# untitled.net
KiCad netlist of a schematic drawn in EAGLE
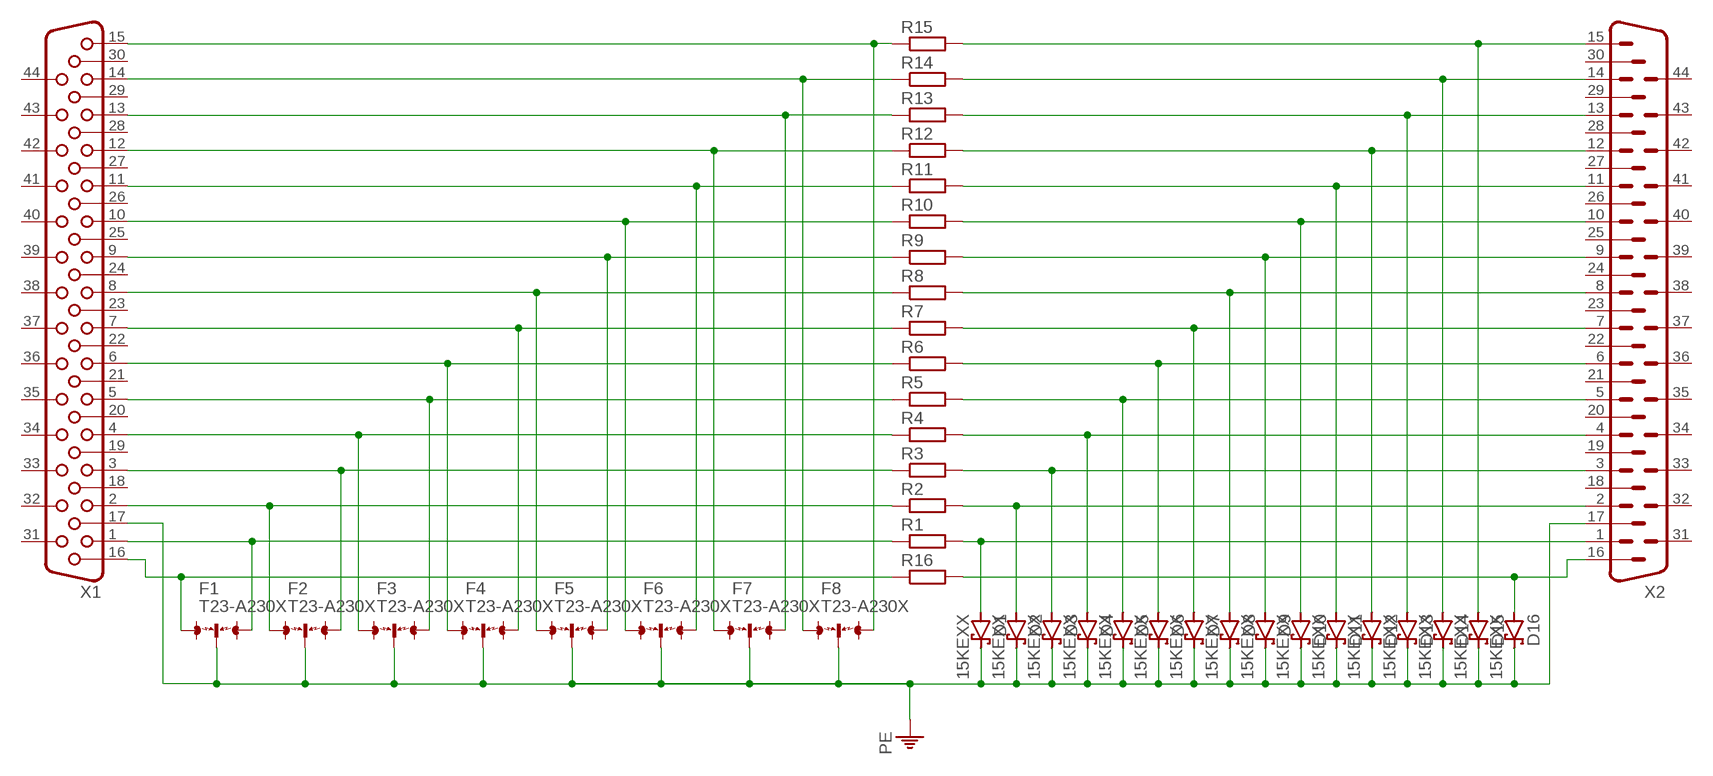
[diagram p0: schematic, sheet 1]

(export (version "E")
  (design (tool "Eeschema 10.0.6"))
  (components
    (comp (ref "D1")
      (value "15KEXX")
      (footprint "eagle-import:CB429-17")
      (libsource (lib "eagle-import") (part "15KEXX"))
    )
    (comp (ref "D2")
      (value "15KEXX")
      (footprint "eagle-import:CB429-17")
      (libsource (lib "eagle-import") (part "15KEXX"))
    )
    (comp (ref "D3")
      (value "15KEXX")
      (footprint "eagle-import:CB429-17")
      (libsource (lib "eagle-import") (part "15KEXX"))
    )
    (comp (ref "D4")
      (value "15KEXX")
      (footprint "eagle-import:CB429-17")
      (libsource (lib "eagle-import") (part "15KEXX"))
    )
    (comp (ref "D5")
      (value "15KEXX")
      (footprint "eagle-import:CB429-17")
      (libsource (lib "eagle-import") (part "15KEXX"))
    )
    (comp (ref "D6")
      (value "15KEXX")
      (footprint "eagle-import:CB429-17")
      (libsource (lib "eagle-import") (part "15KEXX"))
    )
    (comp (ref "D7")
      (value "15KEXX")
      (footprint "eagle-import:CB429-17")
      (libsource (lib "eagle-import") (part "15KEXX"))
    )
    (comp (ref "D8")
      (value "15KEXX")
      (footprint "eagle-import:CB429-17")
      (libsource (lib "eagle-import") (part "15KEXX"))
    )
    (comp (ref "D9")
      (value "15KEXX")
      (footprint "eagle-import:CB429-17")
      (libsource (lib "eagle-import") (part "15KEXX"))
    )
    (comp (ref "D10")
      (value "15KEXX")
      (footprint "eagle-import:CB429-17")
      (libsource (lib "eagle-import") (part "15KEXX"))
    )
    (comp (ref "D11")
      (value "15KEXX")
      (footprint "eagle-import:CB429-17")
      (libsource (lib "eagle-import") (part "15KEXX"))
    )
    (comp (ref "D12")
      (value "15KEXX")
      (footprint "eagle-import:CB429-17")
      (libsource (lib "eagle-import") (part "15KEXX"))
    )
    (comp (ref "D13")
      (value "15KEXX")
      (footprint "eagle-import:CB429-17")
      (libsource (lib "eagle-import") (part "15KEXX"))
    )
    (comp (ref "D14")
      (value "15KEXX")
      (footprint "eagle-import:CB429-17")
      (libsource (lib "eagle-import") (part "15KEXX"))
    )
    (comp (ref "D15")
      (value "15KEXX")
      (footprint "eagle-import:CB429-17")
      (libsource (lib "eagle-import") (part "15KEXX"))
    )
    (comp (ref "D16")
      (value "15KEXX")
      (footprint "eagle-import:CB429-17")
      (libsource (lib "eagle-import") (part "15KEXX"))
    )
    (comp (ref "F1")
      (value "T23-A230X")
      (footprint "eagle-import:T23-A230X")
      (libsource (lib "eagle-import") (part "T23-A230X"))
    )
    (comp (ref "F2")
      (value "T23-A230X")
      (footprint "eagle-import:T23-A230X")
      (libsource (lib "eagle-import") (part "T23-A230X"))
    )
    (comp (ref "F3")
      (value "T23-A230X")
      (footprint "eagle-import:T23-A230X")
      (libsource (lib "eagle-import") (part "T23-A230X"))
    )
    (comp (ref "F4")
      (value "T23-A230X")
      (footprint "eagle-import:T23-A230X")
      (libsource (lib "eagle-import") (part "T23-A230X"))
    )
    (comp (ref "F5")
      (value "T23-A230X")
      (footprint "eagle-import:T23-A230X")
      (libsource (lib "eagle-import") (part "T23-A230X"))
    )
    (comp (ref "F6")
      (value "T23-A230X")
      (footprint "eagle-import:T23-A230X")
      (libsource (lib "eagle-import") (part "T23-A230X"))
    )
    (comp (ref "F7")
      (value "T23-A230X")
      (footprint "eagle-import:T23-A230X")
      (libsource (lib "eagle-import") (part "T23-A230X"))
    )
    (comp (ref "F8")
      (value "T23-A230X")
      (footprint "eagle-import:T23-A230X")
      (libsource (lib "eagle-import") (part "T23-A230X"))
    )
    (comp (ref "R1")
      (value "R-EU_R1210")
      (footprint "eagle-import:R1210")
      (libsource (lib "eagle-import") (part "R-EU_R1210"))
    )
    (comp (ref "R2")
      (value "R-EU_R1210")
      (footprint "eagle-import:R1210")
      (libsource (lib "eagle-import") (part "R-EU_R1210"))
    )
    (comp (ref "R3")
      (value "R-EU_R1210")
      (footprint "eagle-import:R1210")
      (libsource (lib "eagle-import") (part "R-EU_R1210"))
    )
    (comp (ref "R4")
      (value "R-EU_R1210")
      (footprint "eagle-import:R1210")
      (libsource (lib "eagle-import") (part "R-EU_R1210"))
    )
    (comp (ref "R5")
      (value "R-EU_R1210")
      (footprint "eagle-import:R1210")
      (libsource (lib "eagle-import") (part "R-EU_R1210"))
    )
    (comp (ref "R6")
      (value "R-EU_R1210")
      (footprint "eagle-import:R1210")
      (libsource (lib "eagle-import") (part "R-EU_R1210"))
    )
    (comp (ref "R7")
      (value "R-EU_R1210")
      (footprint "eagle-import:R1210")
      (libsource (lib "eagle-import") (part "R-EU_R1210"))
    )
    (comp (ref "R8")
      (value "R-EU_R1210")
      (footprint "eagle-import:R1210")
      (libsource (lib "eagle-import") (part "R-EU_R1210"))
    )
    (comp (ref "R9")
      (value "R-EU_R1210")
      (footprint "eagle-import:R1210")
      (libsource (lib "eagle-import") (part "R-EU_R1210"))
    )
    (comp (ref "R10")
      (value "R-EU_R1210")
      (footprint "eagle-import:R1210")
      (libsource (lib "eagle-import") (part "R-EU_R1210"))
    )
    (comp (ref "R11")
      (value "R-EU_R1210")
      (footprint "eagle-import:R1210")
      (libsource (lib "eagle-import") (part "R-EU_R1210"))
    )
    (comp (ref "R12")
      (value "R-EU_R1210")
      (footprint "eagle-import:R1210")
      (libsource (lib "eagle-import") (part "R-EU_R1210"))
    )
    (comp (ref "R13")
      (value "R-EU_R1210")
      (footprint "eagle-import:R1210")
      (libsource (lib "eagle-import") (part "R-EU_R1210"))
    )
    (comp (ref "R14")
      (value "R-EU_R1210")
      (footprint "eagle-import:R1210")
      (libsource (lib "eagle-import") (part "R-EU_R1210"))
    )
    (comp (ref "R15")
      (value "R-EU_R1210")
      (footprint "eagle-import:R1210")
      (libsource (lib "eagle-import") (part "R-EU_R1210"))
    )
    (comp (ref "R16")
      (value "R-EU_R1210")
      (footprint "eagle-import:R1210")
      (libsource (lib "eagle-import") (part "R-EU_R1210"))
    )
    (comp (ref "X1")
      (value "HF44H")
      (footprint "eagle-import:HDF44H")
      (libsource (lib "eagle-import") (part "HF44H"))
    )
    (comp (ref "X2")
      (value "HM44H")
      (footprint "eagle-import:HDM44H")
      (libsource (lib "eagle-import") (part "HM44H"))
    )
  )
  (nets
    (net (code "1") (name "Net-(D1-PadA)") (class "Default")
      (node (ref "D1") (pin "A") (pinfunction "A_A") (pintype "passive"))
      (node (ref "R1") (pin "2") (pinfunction "2_2") (pintype "passive"))
      (node (ref "X2") (pin "1") (pinfunction "1_1") (pintype "passive"))
    )
    (net (code "2") (name "Net-(D2-PadA)") (class "Default")
      (node (ref "D2") (pin "A") (pinfunction "A_A") (pintype "passive"))
      (node (ref "R2") (pin "2") (pinfunction "2_2") (pintype "passive"))
      (node (ref "X2") (pin "2") (pinfunction "2_2") (pintype "passive"))
    )
    (net (code "3") (name "Net-(D3-PadA)") (class "Default")
      (node (ref "D3") (pin "A") (pinfunction "A_A") (pintype "passive"))
      (node (ref "R3") (pin "2") (pinfunction "2_2") (pintype "passive"))
      (node (ref "X2") (pin "3") (pinfunction "3_3") (pintype "passive"))
    )
    (net (code "4") (name "Net-(D4-PadA)") (class "Default")
      (node (ref "D4") (pin "A") (pinfunction "A_A") (pintype "passive"))
      (node (ref "R4") (pin "2") (pinfunction "2_2") (pintype "passive"))
      (node (ref "X2") (pin "4") (pinfunction "4_4") (pintype "passive"))
    )
    (net (code "5") (name "Net-(D5-PadA)") (class "Default")
      (node (ref "D5") (pin "A") (pinfunction "A_A") (pintype "passive"))
      (node (ref "R5") (pin "2") (pinfunction "2_2") (pintype "passive"))
      (node (ref "X2") (pin "5") (pinfunction "5_5") (pintype "passive"))
    )
    (net (code "6") (name "Net-(D6-PadA)") (class "Default")
      (node (ref "D6") (pin "A") (pinfunction "A_A") (pintype "passive"))
      (node (ref "R6") (pin "2") (pinfunction "2_2") (pintype "passive"))
      (node (ref "X2") (pin "6") (pinfunction "6_6") (pintype "passive"))
    )
    (net (code "7") (name "Net-(D7-PadA)") (class "Default")
      (node (ref "D7") (pin "A") (pinfunction "A_A") (pintype "passive"))
      (node (ref "R7") (pin "2") (pinfunction "2_2") (pintype "passive"))
      (node (ref "X2") (pin "7") (pinfunction "7_7") (pintype "passive"))
    )
    (net (code "8") (name "Net-(D8-PadA)") (class "Default")
      (node (ref "D8") (pin "A") (pinfunction "A_A") (pintype "passive"))
      (node (ref "R8") (pin "2") (pinfunction "2_2") (pintype "passive"))
      (node (ref "X2") (pin "8") (pinfunction "8_8") (pintype "passive"))
    )
    (net (code "9") (name "Net-(D9-PadA)") (class "Default")
      (node (ref "D9") (pin "A") (pinfunction "A_A") (pintype "passive"))
      (node (ref "R9") (pin "2") (pinfunction "2_2") (pintype "passive"))
      (node (ref "X2") (pin "9") (pinfunction "9_9") (pintype "passive"))
    )
    (net (code "10") (name "Net-(D10-PadA)") (class "Default")
      (node (ref "D10") (pin "A") (pinfunction "A_A") (pintype "passive"))
      (node (ref "R10") (pin "2") (pinfunction "2_2") (pintype "passive"))
      (node (ref "X2") (pin "10") (pinfunction "10_10") (pintype "passive"))
    )
    (net (code "11") (name "Net-(D11-PadA)") (class "Default")
      (node (ref "D11") (pin "A") (pinfunction "A_A") (pintype "passive"))
      (node (ref "R11") (pin "2") (pinfunction "2_2") (pintype "passive"))
      (node (ref "X2") (pin "11") (pinfunction "11_11") (pintype "passive"))
    )
    (net (code "12") (name "Net-(D12-PadA)") (class "Default")
      (node (ref "D12") (pin "A") (pinfunction "A_A") (pintype "passive"))
      (node (ref "R12") (pin "2") (pinfunction "2_2") (pintype "passive"))
      (node (ref "X2") (pin "12") (pinfunction "12_12") (pintype "passive"))
    )
    (net (code "13") (name "Net-(D13-PadA)") (class "Default")
      (node (ref "D13") (pin "A") (pinfunction "A_A") (pintype "passive"))
      (node (ref "R13") (pin "2") (pinfunction "2_2") (pintype "passive"))
      (node (ref "X2") (pin "13") (pinfunction "13_13") (pintype "passive"))
    )
    (net (code "14") (name "Net-(D14-PadA)") (class "Default")
      (node (ref "D14") (pin "A") (pinfunction "A_A") (pintype "passive"))
      (node (ref "R14") (pin "2") (pinfunction "2_2") (pintype "passive"))
      (node (ref "X2") (pin "14") (pinfunction "14_14") (pintype "passive"))
    )
    (net (code "15") (name "Net-(D15-PadA)") (class "Default")
      (node (ref "D15") (pin "A") (pinfunction "A_A") (pintype "passive"))
      (node (ref "R15") (pin "2") (pinfunction "2_2") (pintype "passive"))
      (node (ref "X2") (pin "15") (pinfunction "15_15") (pintype "passive"))
    )
    (net (code "16") (name "Net-(D16-PadA)") (class "Default")
      (node (ref "D16") (pin "A") (pinfunction "A_A") (pintype "passive"))
      (node (ref "R16") (pin "2") (pinfunction "2_2") (pintype "passive"))
      (node (ref "X2") (pin "16") (pinfunction "16_16") (pintype "passive"))
    )
    (net (code "17") (name "Net-(F1-Pad1)") (class "Default")
      (node (ref "F1") (pin "1") (pinfunction "1_1") (pintype "passive"))
      (node (ref "R16") (pin "1") (pinfunction "1_1") (pintype "passive"))
      (node (ref "X1") (pin "16") (pinfunction "16_16") (pintype "passive"))
    )
    (net (code "18") (name "Net-(F1-Pad3)") (class "Default")
      (node (ref "F1") (pin "3") (pinfunction "3_3") (pintype "passive"))
      (node (ref "R1") (pin "1") (pinfunction "1_1") (pintype "passive"))
      (node (ref "X1") (pin "1") (pinfunction "1_1") (pintype "passive"))
    )
    (net (code "19") (name "Net-(F2-Pad1)") (class "Default")
      (node (ref "F2") (pin "1") (pinfunction "1_1") (pintype "passive"))
      (node (ref "R2") (pin "1") (pinfunction "1_1") (pintype "passive"))
      (node (ref "X1") (pin "2") (pinfunction "2_2") (pintype "passive"))
    )
    (net (code "20") (name "Net-(F2-Pad3)") (class "Default")
      (node (ref "F2") (pin "3") (pinfunction "3_3") (pintype "passive"))
      (node (ref "R3") (pin "1") (pinfunction "1_1") (pintype "passive"))
      (node (ref "X1") (pin "3") (pinfunction "3_3") (pintype "passive"))
    )
    (net (code "21") (name "Net-(F3-Pad1)") (class "Default")
      (node (ref "F3") (pin "1") (pinfunction "1_1") (pintype "passive"))
      (node (ref "R4") (pin "1") (pinfunction "1_1") (pintype "passive"))
      (node (ref "X1") (pin "4") (pinfunction "4_4") (pintype "passive"))
    )
    (net (code "22") (name "Net-(F3-Pad3)") (class "Default")
      (node (ref "F3") (pin "3") (pinfunction "3_3") (pintype "passive"))
      (node (ref "R5") (pin "1") (pinfunction "1_1") (pintype "passive"))
      (node (ref "X1") (pin "5") (pinfunction "5_5") (pintype "passive"))
    )
    (net (code "23") (name "Net-(F4-Pad1)") (class "Default")
      (node (ref "F4") (pin "1") (pinfunction "1_1") (pintype "passive"))
      (node (ref "R6") (pin "1") (pinfunction "1_1") (pintype "passive"))
      (node (ref "X1") (pin "6") (pinfunction "6_6") (pintype "passive"))
    )
    (net (code "24") (name "Net-(F4-Pad3)") (class "Default")
      (node (ref "F4") (pin "3") (pinfunction "3_3") (pintype "passive"))
      (node (ref "R7") (pin "1") (pinfunction "1_1") (pintype "passive"))
      (node (ref "X1") (pin "7") (pinfunction "7_7") (pintype "passive"))
    )
    (net (code "25") (name "Net-(F5-Pad1)") (class "Default")
      (node (ref "F5") (pin "1") (pinfunction "1_1") (pintype "passive"))
      (node (ref "R8") (pin "1") (pinfunction "1_1") (pintype "passive"))
      (node (ref "X1") (pin "8") (pinfunction "8_8") (pintype "passive"))
    )
    (net (code "26") (name "Net-(F5-Pad3)") (class "Default")
      (node (ref "F5") (pin "3") (pinfunction "3_3") (pintype "passive"))
      (node (ref "R9") (pin "1") (pinfunction "1_1") (pintype "passive"))
      (node (ref "X1") (pin "9") (pinfunction "9_9") (pintype "passive"))
    )
    (net (code "27") (name "Net-(F6-Pad1)") (class "Default")
      (node (ref "F6") (pin "1") (pinfunction "1_1") (pintype "passive"))
      (node (ref "R10") (pin "1") (pinfunction "1_1") (pintype "passive"))
      (node (ref "X1") (pin "10") (pinfunction "10_10") (pintype "passive"))
    )
    (net (code "28") (name "Net-(F6-Pad3)") (class "Default")
      (node (ref "F6") (pin "3") (pinfunction "3_3") (pintype "passive"))
      (node (ref "R11") (pin "1") (pinfunction "1_1") (pintype "passive"))
      (node (ref "X1") (pin "11") (pinfunction "11_11") (pintype "passive"))
    )
    (net (code "29") (name "Net-(F7-Pad1)") (class "Default")
      (node (ref "F7") (pin "1") (pinfunction "1_1") (pintype "passive"))
      (node (ref "R12") (pin "1") (pinfunction "1_1") (pintype "passive"))
      (node (ref "X1") (pin "12") (pinfunction "12_12") (pintype "passive"))
    )
    (net (code "30") (name "Net-(F7-Pad3)") (class "Default")
      (node (ref "F7") (pin "3") (pinfunction "3_3") (pintype "passive"))
      (node (ref "R13") (pin "1") (pinfunction "1_1") (pintype "passive"))
      (node (ref "X1") (pin "13") (pinfunction "13_13") (pintype "passive"))
    )
    (net (code "31") (name "Net-(F8-Pad1)") (class "Default")
      (node (ref "F8") (pin "1") (pinfunction "1_1") (pintype "passive"))
      (node (ref "R14") (pin "1") (pinfunction "1_1") (pintype "passive"))
      (node (ref "X1") (pin "14") (pinfunction "14_14") (pintype "passive"))
    )
    (net (code "32") (name "Net-(F8-Pad3)") (class "Default")
      (node (ref "F8") (pin "3") (pinfunction "3_3") (pintype "passive"))
      (node (ref "R15") (pin "1") (pinfunction "1_1") (pintype "passive"))
      (node (ref "X1") (pin "15") (pinfunction "15_15") (pintype "passive"))
    )
    (net (code "33") (name "PE") (class "Default")
      (node (ref "D1") (pin "C") (pinfunction "C_C") (pintype "passive"))
      (node (ref "D10") (pin "C") (pinfunction "C_C") (pintype "passive"))
      (node (ref "D11") (pin "C") (pinfunction "C_C") (pintype "passive"))
      (node (ref "D12") (pin "C") (pinfunction "C_C") (pintype "passive"))
      (node (ref "D13") (pin "C") (pinfunction "C_C") (pintype "passive"))
      (node (ref "D14") (pin "C") (pinfunction "C_C") (pintype "passive"))
      (node (ref "D15") (pin "C") (pinfunction "C_C") (pintype "passive"))
      (node (ref "D16") (pin "C") (pinfunction "C_C") (pintype "passive"))
      (node (ref "D2") (pin "C") (pinfunction "C_C") (pintype "passive"))
      (node (ref "D3") (pin "C") (pinfunction "C_C") (pintype "passive"))
      (node (ref "D4") (pin "C") (pinfunction "C_C") (pintype "passive"))
      (node (ref "D5") (pin "C") (pinfunction "C_C") (pintype "passive"))
      (node (ref "D6") (pin "C") (pinfunction "C_C") (pintype "passive"))
      (node (ref "D7") (pin "C") (pinfunction "C_C") (pintype "passive"))
      (node (ref "D8") (pin "C") (pinfunction "C_C") (pintype "passive"))
      (node (ref "D9") (pin "C") (pinfunction "C_C") (pintype "passive"))
      (node (ref "F1") (pin "2") (pinfunction "2_2") (pintype "passive"))
      (node (ref "F2") (pin "2") (pinfunction "2_2") (pintype "passive"))
      (node (ref "F3") (pin "2") (pinfunction "2_2") (pintype "passive"))
      (node (ref "F4") (pin "2") (pinfunction "2_2") (pintype "passive"))
      (node (ref "F5") (pin "2") (pinfunction "2_2") (pintype "passive"))
      (node (ref "F6") (pin "2") (pinfunction "2_2") (pintype "passive"))
      (node (ref "F7") (pin "2") (pinfunction "2_2") (pintype "passive"))
      (node (ref "F8") (pin "2") (pinfunction "2_2") (pintype "passive"))
      (node (ref "X1") (pin "17") (pinfunction "17_17") (pintype "passive"))
      (node (ref "X2") (pin "17") (pinfunction "17_17") (pintype "passive"))
    )
    (net (code "34") (name "unconnected-(X1-Pad18)") (class "Default")
      (node (ref "X1") (pin "18") (pinfunction "18_18") (pintype "passive"))
    )
    (net (code "35") (name "unconnected-(X1-Pad19)") (class "Default")
      (node (ref "X1") (pin "19") (pinfunction "19_19") (pintype "passive"))
    )
    (net (code "36") (name "unconnected-(X1-Pad20)") (class "Default")
      (node (ref "X1") (pin "20") (pinfunction "20_20") (pintype "passive"))
    )
    (net (code "37") (name "unconnected-(X1-Pad21)") (class "Default")
      (node (ref "X1") (pin "21") (pinfunction "21_21") (pintype "passive"))
    )
    (net (code "38") (name "unconnected-(X1-Pad22)") (class "Default")
      (node (ref "X1") (pin "22") (pinfunction "22_22") (pintype "passive"))
    )
    (net (code "39") (name "unconnected-(X1-Pad23)") (class "Default")
      (node (ref "X1") (pin "23") (pinfunction "23_23") (pintype "passive"))
    )
    (net (code "40") (name "unconnected-(X1-Pad24)") (class "Default")
      (node (ref "X1") (pin "24") (pinfunction "24_24") (pintype "passive"))
    )
    (net (code "41") (name "unconnected-(X1-Pad25)") (class "Default")
      (node (ref "X1") (pin "25") (pinfunction "25_25") (pintype "passive"))
    )
    (net (code "42") (name "unconnected-(X1-Pad26)") (class "Default")
      (node (ref "X1") (pin "26") (pinfunction "26_26") (pintype "passive"))
    )
    (net (code "43") (name "unconnected-(X1-Pad27)") (class "Default")
      (node (ref "X1") (pin "27") (pinfunction "27_27") (pintype "passive"))
    )
    (net (code "44") (name "unconnected-(X1-Pad28)") (class "Default")
      (node (ref "X1") (pin "28") (pinfunction "28_28") (pintype "passive"))
    )
    (net (code "45") (name "unconnected-(X1-Pad29)") (class "Default")
      (node (ref "X1") (pin "29") (pinfunction "29_29") (pintype "passive"))
    )
    (net (code "46") (name "unconnected-(X1-Pad30)") (class "Default")
      (node (ref "X1") (pin "30") (pinfunction "30_30") (pintype "passive"))
    )
    (net (code "47") (name "unconnected-(X1-Pad31)") (class "Default")
      (node (ref "X1") (pin "31") (pinfunction "31_31") (pintype "passive"))
    )
    (net (code "48") (name "unconnected-(X1-Pad32)") (class "Default")
      (node (ref "X1") (pin "32") (pinfunction "32_32") (pintype "passive"))
    )
    (net (code "49") (name "unconnected-(X1-Pad33)") (class "Default")
      (node (ref "X1") (pin "33") (pinfunction "33_33") (pintype "passive"))
    )
    (net (code "50") (name "unconnected-(X1-Pad34)") (class "Default")
      (node (ref "X1") (pin "34") (pinfunction "34_34") (pintype "passive"))
    )
    (net (code "51") (name "unconnected-(X1-Pad35)") (class "Default")
      (node (ref "X1") (pin "35") (pinfunction "35_35") (pintype "passive"))
    )
    (net (code "52") (name "unconnected-(X1-Pad36)") (class "Default")
      (node (ref "X1") (pin "36") (pinfunction "36_36") (pintype "passive"))
    )
    (net (code "53") (name "unconnected-(X1-Pad37)") (class "Default")
      (node (ref "X1") (pin "37") (pinfunction "37_37") (pintype "passive"))
    )
    (net (code "54") (name "unconnected-(X1-Pad38)") (class "Default")
      (node (ref "X1") (pin "38") (pinfunction "38_38") (pintype "passive"))
    )
    (net (code "55") (name "unconnected-(X1-Pad39)") (class "Default")
      (node (ref "X1") (pin "39") (pinfunction "39_39") (pintype "passive"))
    )
    (net (code "56") (name "unconnected-(X1-Pad40)") (class "Default")
      (node (ref "X1") (pin "40") (pinfunction "40_40") (pintype "passive"))
    )
    (net (code "57") (name "unconnected-(X1-Pad41)") (class "Default")
      (node (ref "X1") (pin "41") (pinfunction "41_41") (pintype "passive"))
    )
    (net (code "58") (name "unconnected-(X1-Pad42)") (class "Default")
      (node (ref "X1") (pin "42") (pinfunction "42_42") (pintype "passive"))
    )
    (net (code "59") (name "unconnected-(X1-Pad43)") (class "Default")
      (node (ref "X1") (pin "43") (pinfunction "43_43") (pintype "passive"))
    )
    (net (code "60") (name "unconnected-(X1-Pad44)") (class "Default")
      (node (ref "X1") (pin "44") (pinfunction "44_44") (pintype "passive"))
    )
    (net (code "61") (name "unconnected-(X2-Pad18)") (class "Default")
      (node (ref "X2") (pin "18") (pinfunction "18_18") (pintype "passive"))
    )
    (net (code "62") (name "unconnected-(X2-Pad19)") (class "Default")
      (node (ref "X2") (pin "19") (pinfunction "19_19") (pintype "passive"))
    )
    (net (code "63") (name "unconnected-(X2-Pad20)") (class "Default")
      (node (ref "X2") (pin "20") (pinfunction "20_20") (pintype "passive"))
    )
    (net (code "64") (name "unconnected-(X2-Pad21)") (class "Default")
      (node (ref "X2") (pin "21") (pinfunction "21_21") (pintype "passive"))
    )
    (net (code "65") (name "unconnected-(X2-Pad22)") (class "Default")
      (node (ref "X2") (pin "22") (pinfunction "22_22") (pintype "passive"))
    )
    (net (code "66") (name "unconnected-(X2-Pad23)") (class "Default")
      (node (ref "X2") (pin "23") (pinfunction "23_23") (pintype "passive"))
    )
    (net (code "67") (name "unconnected-(X2-Pad24)") (class "Default")
      (node (ref "X2") (pin "24") (pinfunction "24_24") (pintype "passive"))
    )
    (net (code "68") (name "unconnected-(X2-Pad25)") (class "Default")
      (node (ref "X2") (pin "25") (pinfunction "25_25") (pintype "passive"))
    )
    (net (code "69") (name "unconnected-(X2-Pad26)") (class "Default")
      (node (ref "X2") (pin "26") (pinfunction "26_26") (pintype "passive"))
    )
    (net (code "70") (name "unconnected-(X2-Pad27)") (class "Default")
      (node (ref "X2") (pin "27") (pinfunction "27_27") (pintype "passive"))
    )
    (net (code "71") (name "unconnected-(X2-Pad28)") (class "Default")
      (node (ref "X2") (pin "28") (pinfunction "28_28") (pintype "passive"))
    )
    (net (code "72") (name "unconnected-(X2-Pad29)") (class "Default")
      (node (ref "X2") (pin "29") (pinfunction "29_29") (pintype "passive"))
    )
    (net (code "73") (name "unconnected-(X2-Pad30)") (class "Default")
      (node (ref "X2") (pin "30") (pinfunction "30_30") (pintype "passive"))
    )
    (net (code "74") (name "unconnected-(X2-Pad31)") (class "Default")
      (node (ref "X2") (pin "31") (pinfunction "31_31") (pintype "passive"))
    )
    (net (code "75") (name "unconnected-(X2-Pad32)") (class "Default")
      (node (ref "X2") (pin "32") (pinfunction "32_32") (pintype "passive"))
    )
    (net (code "76") (name "unconnected-(X2-Pad33)") (class "Default")
      (node (ref "X2") (pin "33") (pinfunction "33_33") (pintype "passive"))
    )
    (net (code "77") (name "unconnected-(X2-Pad34)") (class "Default")
      (node (ref "X2") (pin "34") (pinfunction "34_34") (pintype "passive"))
    )
    (net (code "78") (name "unconnected-(X2-Pad35)") (class "Default")
      (node (ref "X2") (pin "35") (pinfunction "35_35") (pintype "passive"))
    )
    (net (code "79") (name "unconnected-(X2-Pad36)") (class "Default")
      (node (ref "X2") (pin "36") (pinfunction "36_36") (pintype "passive"))
    )
    (net (code "80") (name "unconnected-(X2-Pad37)") (class "Default")
      (node (ref "X2") (pin "37") (pinfunction "37_37") (pintype "passive"))
    )
    (net (code "81") (name "unconnected-(X2-Pad38)") (class "Default")
      (node (ref "X2") (pin "38") (pinfunction "38_38") (pintype "passive"))
    )
    (net (code "82") (name "unconnected-(X2-Pad39)") (class "Default")
      (node (ref "X2") (pin "39") (pinfunction "39_39") (pintype "passive"))
    )
    (net (code "83") (name "unconnected-(X2-Pad40)") (class "Default")
      (node (ref "X2") (pin "40") (pinfunction "40_40") (pintype "passive"))
    )
    (net (code "84") (name "unconnected-(X2-Pad41)") (class "Default")
      (node (ref "X2") (pin "41") (pinfunction "41_41") (pintype "passive"))
    )
    (net (code "85") (name "unconnected-(X2-Pad42)") (class "Default")
      (node (ref "X2") (pin "42") (pinfunction "42_42") (pintype "passive"))
    )
    (net (code "86") (name "unconnected-(X2-Pad43)") (class "Default")
      (node (ref "X2") (pin "43") (pinfunction "43_43") (pintype "passive"))
    )
    (net (code "87") (name "unconnected-(X2-Pad44)") (class "Default")
      (node (ref "X2") (pin "44") (pinfunction "44_44") (pintype "passive"))
    )
  )
)
